# Motorcycle_ECU.net
KiCad netlist of a schematic drawn in Altium Designer
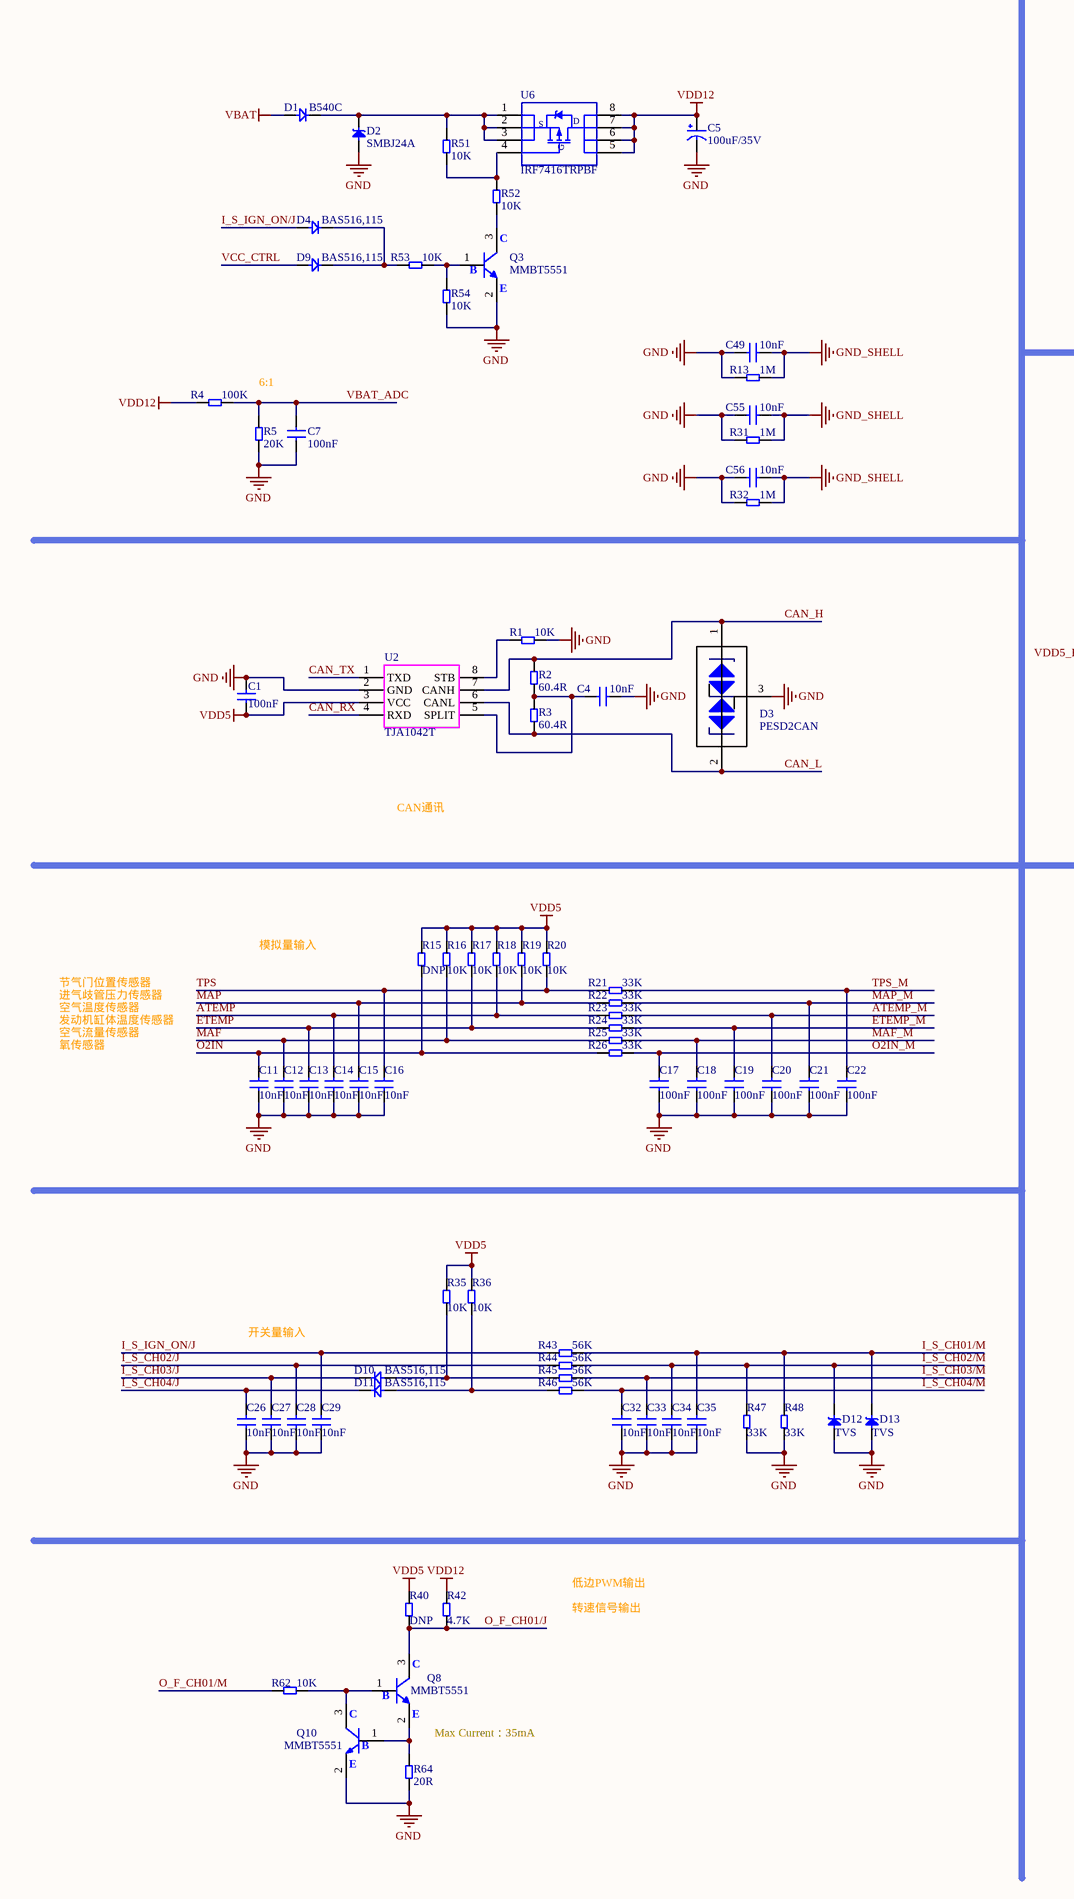
[diagram p0: Motorcycle_ECU.SchDoc, left]
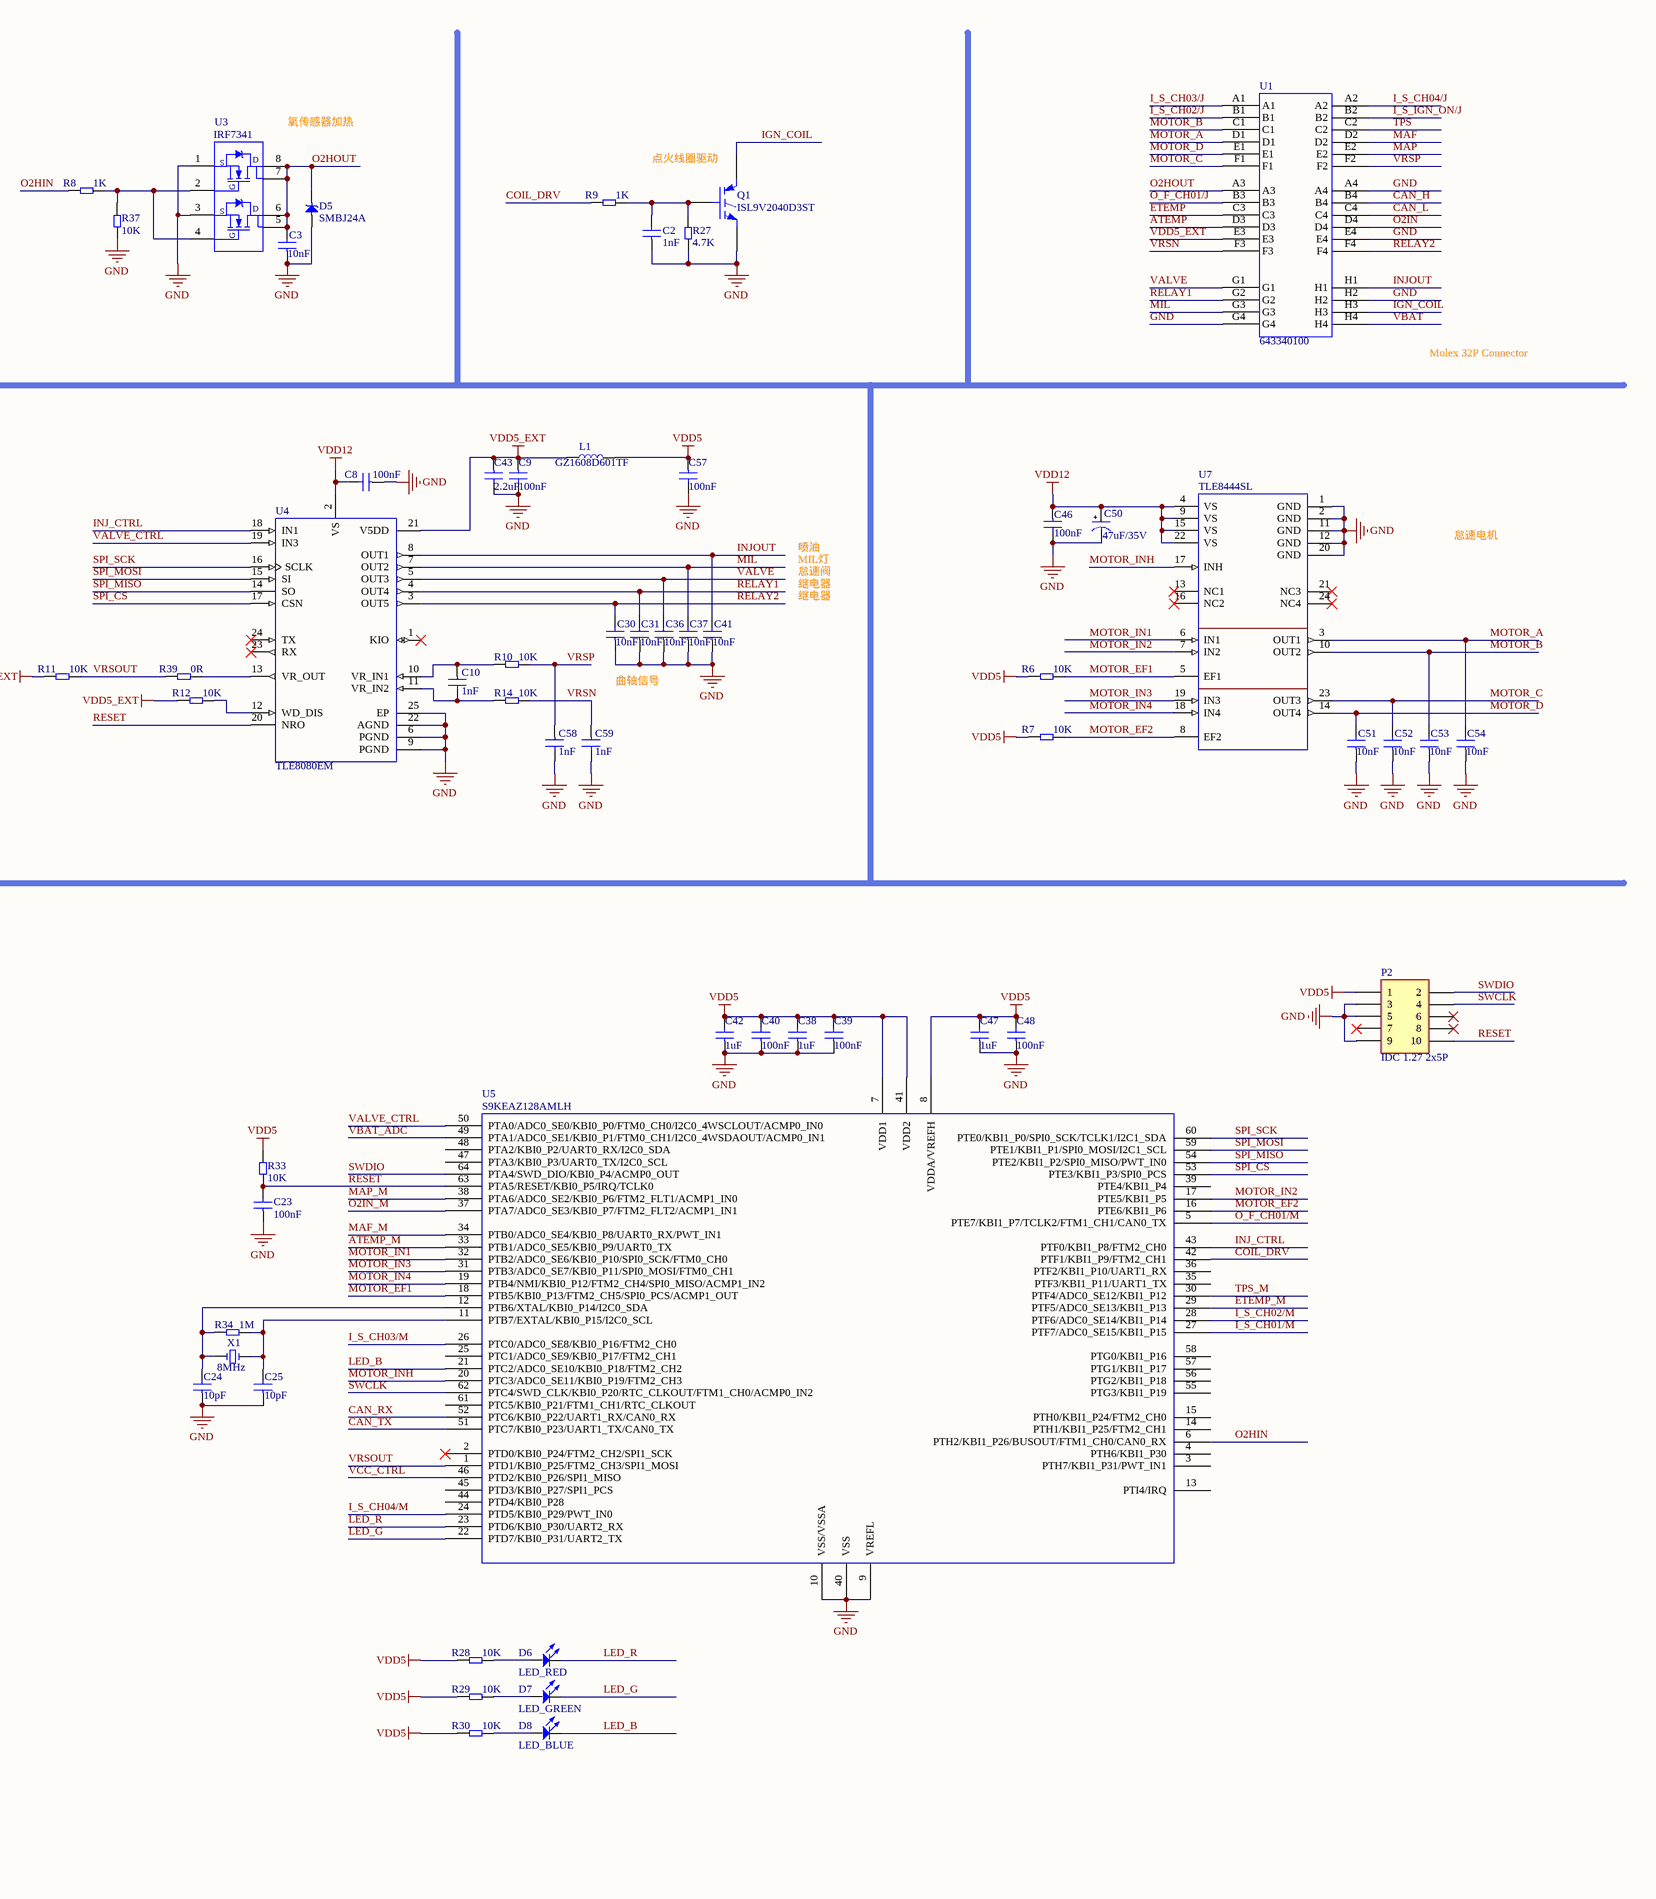
[diagram p1: Motorcycle_ECU.SchDoc, right]

(export (version "E")
  (design (tool "Eeschema 10.0.6"))
  (components
    (comp (ref "C1") (value "100nF") (footprint "C0603") (libsource (lib "mzy2364") (part "CAP")))
    (comp (ref "C2")
      (value "1nF")
      (footprint "C0603")
      (fields (field (name "VOLTAGE") "50V"))
      (libsource (lib "mzy2364") (part "CAP"))
    )
    (comp (ref "C3")
      (value "10nF")
      (footprint "C0603")
      (fields (field (name "VOLTAGE") "50V"))
      (libsource (lib "mzy2364") (part "CAP"))
    )
    (comp (ref "C4") (value "10nF") (footprint "C0603") (libsource (lib "mzy2364") (part "CAP")))
    (comp (ref "C5")
      (value "100uF/35V")
      (footprint "CM E(8*10.2)")
      (libsource (lib "mzy2364") (part "C POL"))
    )
    (comp (ref "C7")
      (value "100nF")
      (footprint "C0603")
      (fields (field (name "VOLTAGE") "50V"))
      (libsource (lib "mzy2364") (part "CAP"))
    )
    (comp (ref "C8")
      (value "100nF")
      (footprint "C0603")
      (fields (field (name "VOLTAGE") "50V"))
      (libsource (lib "mzy2364") (part "CAP"))
    )
    (comp (ref "C9")
      (value "100nF")
      (footprint "C0603")
      (fields (field (name "VOLTAGE") "50V"))
      (libsource (lib "mzy2364") (part "CAP"))
    )
    (comp (ref "C10")
      (value "1nF")
      (footprint "C0603")
      (fields (field (name "VOLTAGE") "50V"))
      (libsource (lib "mzy2364") (part "CAP"))
    )
    (comp (ref "C11")
      (value "10nF")
      (footprint "C0603")
      (fields (field (name "VOLTAGE") "50V"))
      (libsource (lib "mzy2364") (part "CAP"))
    )
    (comp (ref "C12")
      (value "10nF")
      (footprint "C0603")
      (fields (field (name "VOLTAGE") "50V"))
      (libsource (lib "mzy2364") (part "CAP"))
    )
    (comp (ref "C13")
      (value "10nF")
      (footprint "C0603")
      (fields (field (name "VOLTAGE") "50V"))
      (libsource (lib "mzy2364") (part "CAP"))
    )
    (comp (ref "C14")
      (value "10nF")
      (footprint "C0603")
      (fields (field (name "VOLTAGE") "50V"))
      (libsource (lib "mzy2364") (part "CAP"))
    )
    (comp (ref "C15")
      (value "10nF")
      (footprint "C0603")
      (fields (field (name "VOLTAGE") "50V"))
      (libsource (lib "mzy2364") (part "CAP"))
    )
    (comp (ref "C16")
      (value "10nF")
      (footprint "C0603")
      (fields (field (name "VOLTAGE") "50V"))
      (libsource (lib "mzy2364") (part "CAP"))
    )
    (comp (ref "C17")
      (value "100nF")
      (footprint "C0603")
      (fields (field (name "VOLTAGE") "50V"))
      (libsource (lib "mzy2364") (part "CAP"))
    )
    (comp (ref "C18")
      (value "100nF")
      (footprint "C0603")
      (fields (field (name "VOLTAGE") "50V"))
      (libsource (lib "mzy2364") (part "CAP"))
    )
    (comp (ref "C19")
      (value "100nF")
      (footprint "C0603")
      (fields (field (name "VOLTAGE") "50V"))
      (libsource (lib "mzy2364") (part "CAP"))
    )
    (comp (ref "C20")
      (value "100nF")
      (footprint "C0603")
      (fields (field (name "VOLTAGE") "50V"))
      (libsource (lib "mzy2364") (part "CAP"))
    )
    (comp (ref "C21")
      (value "100nF")
      (footprint "C0603")
      (fields (field (name "VOLTAGE") "50V"))
      (libsource (lib "mzy2364") (part "CAP"))
    )
    (comp (ref "C22")
      (value "100nF")
      (footprint "C0603")
      (fields (field (name "VOLTAGE") "50V"))
      (libsource (lib "mzy2364") (part "CAP"))
    )
    (comp (ref "C23")
      (value "100nF")
      (footprint "C0603")
      (fields (field (name "VOLTAGE") "50V"))
      (libsource (lib "mzy2364") (part "CAP"))
    )
    (comp (ref "C24") (value "10pF") (footprint "C0603") (libsource (lib "mzy2364") (part "CAP")))
    (comp (ref "C25") (value "10pF") (footprint "C0603") (libsource (lib "mzy2364") (part "CAP")))
    (comp (ref "C26")
      (value "10nF")
      (footprint "C0603")
      (fields (field (name "VOLTAGE") "50V"))
      (libsource (lib "mzy2364") (part "CAP"))
    )
    (comp (ref "C27")
      (value "10nF")
      (footprint "C0603")
      (fields (field (name "VOLTAGE") "50V"))
      (libsource (lib "mzy2364") (part "CAP"))
    )
    (comp (ref "C28")
      (value "10nF")
      (footprint "C0603")
      (fields (field (name "VOLTAGE") "50V"))
      (libsource (lib "mzy2364") (part "CAP"))
    )
    (comp (ref "C29")
      (value "10nF")
      (footprint "C0603")
      (fields (field (name "VOLTAGE") "50V"))
      (libsource (lib "mzy2364") (part "CAP"))
    )
    (comp (ref "C30")
      (value "10nF")
      (footprint "C0603")
      (fields (field (name "VOLTAGE") "50V"))
      (libsource (lib "mzy2364") (part "CAP"))
    )
    (comp (ref "C31")
      (value "10nF")
      (footprint "C0603")
      (fields (field (name "VOLTAGE") "50V"))
      (libsource (lib "mzy2364") (part "CAP"))
    )
    (comp (ref "C32")
      (value "10nF")
      (footprint "C0603")
      (fields (field (name "VOLTAGE") "50V"))
      (libsource (lib "mzy2364") (part "CAP"))
    )
    (comp (ref "C33")
      (value "10nF")
      (footprint "C0603")
      (fields (field (name "VOLTAGE") "50V"))
      (libsource (lib "mzy2364") (part "CAP"))
    )
    (comp (ref "C34")
      (value "10nF")
      (footprint "C0603")
      (fields (field (name "VOLTAGE") "50V"))
      (libsource (lib "mzy2364") (part "CAP"))
    )
    (comp (ref "C35")
      (value "10nF")
      (footprint "C0603")
      (fields (field (name "VOLTAGE") "50V"))
      (libsource (lib "mzy2364") (part "CAP"))
    )
    (comp (ref "C36")
      (value "10nF")
      (footprint "C0603")
      (fields (field (name "VOLTAGE") "50V"))
      (libsource (lib "mzy2364") (part "CAP"))
    )
    (comp (ref "C37")
      (value "10nF")
      (footprint "C0603")
      (fields (field (name "VOLTAGE") "50V"))
      (libsource (lib "mzy2364") (part "CAP"))
    )
    (comp (ref "C38")
      (value "1uF")
      (footprint "C0603")
      (fields (field (name "VOLTAGE") "50V"))
      (libsource (lib "mzy2364") (part "CAP"))
    )
    (comp (ref "C39")
      (value "100nF")
      (footprint "C0603")
      (fields (field (name "VOLTAGE") "50V"))
      (libsource (lib "mzy2364") (part "CAP"))
    )
    (comp (ref "C40")
      (value "100nF")
      (footprint "C0603")
      (fields (field (name "VOLTAGE") "50V"))
      (libsource (lib "mzy2364") (part "CAP"))
    )
    (comp (ref "C41")
      (value "10nF")
      (footprint "C0603")
      (fields (field (name "VOLTAGE") "50V"))
      (libsource (lib "mzy2364") (part "CAP"))
    )
    (comp (ref "C42")
      (value "1uF")
      (footprint "C0603")
      (fields (field (name "VOLTAGE") "50V"))
      (libsource (lib "mzy2364") (part "CAP"))
    )
    (comp (ref "C43")
      (value "2.2uF")
      (footprint "C0603")
      (fields (field (name "VOLTAGE") "50V"))
      (libsource (lib "mzy2364") (part "CAP"))
    )
    (comp (ref "C46")
      (value "100nF")
      (footprint "C0603")
      (fields (field (name "VOLTAGE") "50V"))
      (libsource (lib "mzy2364") (part "CAP"))
    )
    (comp (ref "C47")
      (value "1uF")
      (footprint "C0603")
      (fields (field (name "VOLTAGE") "50V"))
      (libsource (lib "mzy2364") (part "CAP"))
    )
    (comp (ref "C48")
      (value "100nF")
      (footprint "C0603")
      (fields (field (name "VOLTAGE") "50V"))
      (libsource (lib "mzy2364") (part "CAP"))
    )
    (comp (ref "C49")
      (value "10nF")
      (footprint "C0603")
      (fields (field (name "VOLTAGE") "50V"))
      (libsource (lib "mzy2364") (part "CAP"))
    )
    (comp (ref "C50")
      (value "47uF/35V")
      (footprint "CM D(6.3*7.7)")
      (libsource (lib "mzy2364") (part "C POL"))
    )
    (comp (ref "C51")
      (value "10nF")
      (footprint "C0603")
      (fields (field (name "VOLTAGE") "50V"))
      (libsource (lib "mzy2364") (part "CAP"))
    )
    (comp (ref "C52")
      (value "10nF")
      (footprint "C0603")
      (fields (field (name "VOLTAGE") "50V"))
      (libsource (lib "mzy2364") (part "CAP"))
    )
    (comp (ref "C53")
      (value "10nF")
      (footprint "C0603")
      (fields (field (name "VOLTAGE") "50V"))
      (libsource (lib "mzy2364") (part "CAP"))
    )
    (comp (ref "C54")
      (value "10nF")
      (footprint "C0603")
      (fields (field (name "VOLTAGE") "50V"))
      (libsource (lib "mzy2364") (part "CAP"))
    )
    (comp (ref "C55")
      (value "10nF")
      (footprint "C0603")
      (fields (field (name "VOLTAGE") "50V"))
      (libsource (lib "mzy2364") (part "CAP"))
    )
    (comp (ref "C56")
      (value "10nF")
      (footprint "C0603")
      (fields (field (name "VOLTAGE") "50V"))
      (libsource (lib "mzy2364") (part "CAP"))
    )
    (comp (ref "C57")
      (value "100nF")
      (footprint "C0603")
      (fields (field (name "VOLTAGE") "50V"))
      (libsource (lib "mzy2364") (part "CAP"))
    )
    (comp (ref "C58")
      (value "1nF")
      (footprint "C0603")
      (fields (field (name "VOLTAGE") "50V"))
      (libsource (lib "mzy2364") (part "CAP"))
    )
    (comp (ref "C59")
      (value "1nF")
      (footprint "C0603")
      (fields (field (name "VOLTAGE") "50V"))
      (libsource (lib "mzy2364") (part "CAP"))
    )
    (comp (ref "D1") (value "B540C") (footprint "SMC") (libsource (lib "mzy2364") (part "D")))
    (comp (ref "D2") (value "SMBJ24A") (footprint "SMB") (libsource (lib "mzy2364") (part "D TVS")))
    (comp (ref "D3") (value "PESD2CAN") (footprint "SOT23") (libsource (lib "EDC17_5644A") (part "PESD2CAN")))
    (comp (ref "D4") (value "BAS516,115") (footprint "SOD-523") (libsource (lib "mzy2364") (part "D")))
    (comp (ref "D5") (value "SMBJ24A") (footprint "SMB") (libsource (lib "mzy2364") (part "D TVS")))
    (comp (ref "D6") (value "LED_RED") (footprint "LED 0603") (libsource (lib "mzy2364") (part "LED")))
    (comp (ref "D7") (value "LED_GREEN") (footprint "LED 0603") (libsource (lib "mzy2364") (part "LED")))
    (comp (ref "D8") (value "LED_BLUE") (footprint "LED 0603") (libsource (lib "mzy2364") (part "LED")))
    (comp (ref "D9") (value "BAS516,115") (footprint "SOD-523") (libsource (lib "mzy2364") (part "D")))
    (comp (ref "D10") (value "BAS516,115") (footprint "SOD-523") (libsource (lib "mzy2364") (part "D")))
    (comp (ref "D11") (value "BAS516,115") (footprint "SOD-523") (libsource (lib "mzy2364") (part "D")))
    (comp (ref "D12") (value "TVS") (footprint "SOD-523") (libsource (lib "mzy2364") (part "D TVS")))
    (comp (ref "D13") (value "TVS") (footprint "SOD-523") (libsource (lib "mzy2364") (part "D TVS")))
    (comp (ref "L1") (value "GZ1608D601TF") (footprint "L_0603") (libsource (lib "mzy2364") (part "L")))
    (comp (ref "P2")
      (value "IDC 1.27 2x5P")
      (footprint "IDC-TH_10P-P1.27-X1270WV-2X05A-6TV01")
      (fields (field (name "PUBLISHER") "Altium Limited"))
      (libsource (lib "HRJDB_Lib") (part "Header 5X2"))
    )
    (comp (ref "Q1")
      (value "ISL9V2040D3ST")
      (footprint "TO252")
      (libsource (lib "mzy2364") (part "AOD5B65M1"))
    )
    (comp (ref "Q3") (value "MMBT5551") (footprint "SOT23") (libsource (lib "mzy2364") (part "NPN")))
    (comp (ref "Q8") (value "MMBT5551") (footprint "SOT23") (libsource (lib "mzy2364") (part "NPN")))
    (comp (ref "Q10") (value "MMBT5551") (footprint "SOT23") (libsource (lib "mzy2364") (part "NPN_1")))
    (comp (ref "R1") (value "10K") (footprint "RES0603") (libsource (lib "mzy2364") (part "RES")))
    (comp (ref "R2") (value "60.4R") (footprint "RES0603") (libsource (lib "mzy2364") (part "RES")))
    (comp (ref "R3") (value "60.4R") (footprint "RES0603") (libsource (lib "mzy2364") (part "RES")))
    (comp (ref "R4") (value "100K") (footprint "RES0603") (libsource (lib "mzy2364") (part "RES")))
    (comp (ref "R5") (value "20K") (footprint "RES0603") (libsource (lib "mzy2364") (part "RES")))
    (comp (ref "R6") (value "10K") (footprint "RES0603") (libsource (lib "mzy2364") (part "RES")))
    (comp (ref "R7") (value "10K") (footprint "RES0603") (libsource (lib "mzy2364") (part "RES")))
    (comp (ref "R8") (value "1K") (footprint "RES0603") (libsource (lib "mzy2364") (part "RES")))
    (comp (ref "R9") (value "1K") (footprint "RES0603") (libsource (lib "mzy2364") (part "RES")))
    (comp (ref "R10") (value "10K") (footprint "RES0603") (libsource (lib "mzy2364") (part "RES")))
    (comp (ref "R11") (value "10K") (footprint "RES0603") (libsource (lib "mzy2364") (part "RES")))
    (comp (ref "R12") (value "10K") (footprint "RES0603") (libsource (lib "mzy2364") (part "RES")))
    (comp (ref "R13") (value "1M") (footprint "RES0603") (libsource (lib "mzy2364") (part "RES")))
    (comp (ref "R14") (value "10K") (footprint "RES0603") (libsource (lib "mzy2364") (part "RES")))
    (comp (ref "R15") (value "DNP") (footprint "RES0603") (libsource (lib "mzy2364") (part "RES")))
    (comp (ref "R16") (value "10K") (footprint "RES0603") (libsource (lib "mzy2364") (part "RES")))
    (comp (ref "R17") (value "10K") (footprint "RES0603") (libsource (lib "mzy2364") (part "RES")))
    (comp (ref "R18") (value "10K") (footprint "RES0603") (libsource (lib "mzy2364") (part "RES")))
    (comp (ref "R19") (value "10K") (footprint "RES0603") (libsource (lib "mzy2364") (part "RES")))
    (comp (ref "R20") (value "10K") (footprint "RES0603") (libsource (lib "mzy2364") (part "RES")))
    (comp (ref "R21") (value "33K") (footprint "RES0603") (libsource (lib "mzy2364") (part "RES")))
    (comp (ref "R22") (value "33K") (footprint "RES0603") (libsource (lib "mzy2364") (part "RES")))
    (comp (ref "R23") (value "33K") (footprint "RES0603") (libsource (lib "mzy2364") (part "RES")))
    (comp (ref "R24") (value "33K") (footprint "RES0603") (libsource (lib "mzy2364") (part "RES")))
    (comp (ref "R25") (value "33K") (footprint "RES0603") (libsource (lib "mzy2364") (part "RES")))
    (comp (ref "R26") (value "33K") (footprint "RES0603") (libsource (lib "mzy2364") (part "RES")))
    (comp (ref "R27") (value "4.7K") (footprint "RES0603") (libsource (lib "mzy2364") (part "RES")))
    (comp (ref "R28") (value "10K") (footprint "RES0603") (libsource (lib "mzy2364") (part "RES")))
    (comp (ref "R29") (value "10K") (footprint "RES0603") (libsource (lib "mzy2364") (part "RES")))
    (comp (ref "R30") (value "10K") (footprint "RES0603") (libsource (lib "mzy2364") (part "RES")))
    (comp (ref "R31") (value "1M") (footprint "RES0603") (libsource (lib "mzy2364") (part "RES")))
    (comp (ref "R32") (value "1M") (footprint "RES0603") (libsource (lib "mzy2364") (part "RES")))
    (comp (ref "R33") (value "10K") (footprint "RES0603") (libsource (lib "mzy2364") (part "RES")))
    (comp (ref "R34") (value "1M") (footprint "RES0603") (libsource (lib "mzy2364") (part "RES")))
    (comp (ref "R35") (value "10K") (footprint "RES0603") (libsource (lib "mzy2364") (part "RES")))
    (comp (ref "R36") (value "10K") (footprint "RES0603") (libsource (lib "mzy2364") (part "RES")))
    (comp (ref "R37") (value "10K") (footprint "RES0603") (libsource (lib "mzy2364") (part "RES")))
    (comp (ref "R39") (value "0R") (footprint "RES0603") (libsource (lib "mzy2364") (part "RES")))
    (comp (ref "R40") (value "DNP") (footprint "RES0603") (libsource (lib "mzy2364") (part "RES")))
    (comp (ref "R42") (value "4.7K") (footprint "RES0603") (libsource (lib "mzy2364") (part "RES")))
    (comp (ref "R43") (value "56K") (footprint "RES0603") (libsource (lib "mzy2364") (part "RES")))
    (comp (ref "R44") (value "56K") (footprint "RES0603") (libsource (lib "mzy2364") (part "RES")))
    (comp (ref "R45") (value "56K") (footprint "RES0603") (libsource (lib "mzy2364") (part "RES")))
    (comp (ref "R46") (value "56K") (footprint "RES0603") (libsource (lib "mzy2364") (part "RES")))
    (comp (ref "R47") (value "33K") (footprint "RES0603") (libsource (lib "mzy2364") (part "RES")))
    (comp (ref "R48") (value "33K") (footprint "RES0603") (libsource (lib "mzy2364") (part "RES")))
    (comp (ref "R51") (value "10K") (footprint "RES0603") (libsource (lib "mzy2364") (part "RES")))
    (comp (ref "R52") (value "10K") (footprint "RES0603") (libsource (lib "mzy2364") (part "RES")))
    (comp (ref "R53") (value "10K") (footprint "RES0603") (libsource (lib "mzy2364") (part "RES")))
    (comp (ref "R54") (value "10K") (footprint "RES0603") (libsource (lib "mzy2364") (part "RES")))
    (comp (ref "R62") (value "10K") (footprint "RES0603") (libsource (lib "mzy2364") (part "RES")))
    (comp (ref "R64") (value "20R") (footprint "RES0603") (libsource (lib "mzy2364") (part "RES")))
    (comp (ref "U1")
      (value "643340100")
      (footprint "MOLEX-32P_SHARP_1")
      (description "MOLEX 32P接插件")
      (libsource (lib "mzy2364") (part "643340100"))
    )
    (comp (ref "U2")
      (value "TJA1042T")
      (footprint "SOIC8-150MIL")
      (description "CAN收发器")
      (libsource (lib "mzy2364") (part "TJA1042T"))
    )
    (comp (ref "U3")
      (value "IRF7341")
      (footprint "SOIC8-150MIL")
      (description "NMOS 双通道")
      (libsource (lib "mzy2364") (part "AO4800"))
    )
    (comp (ref "U4")
      (value "TLE8080EM")
      (footprint "INF-PG-SSOP-24-4")
      (description "Engine Management IC for Small Engine, 6 to 18 V Supply, PG-SSOP-24-4, Reel, Green")
      (fields (field (name "MANUFACTURER") "Infineon"))
      (libsource (lib "mzy2364") (part "TLE8080EM"))
    )
    (comp (ref "U5")
      (value "S9KEAZ128AMLH")
      (footprint "LQFP64-0.5")
      (libsource (lib "mzy2364") (part "S9KEAZ64AMLH"))
    )
    (comp (ref "U6")
      (value "IRF7416TRPBF")
      (footprint "SOIC8-150MIL")
      (libsource (lib "mzy2364") (part "FDS4435BZ"))
    )
    (comp (ref "U7")
      (value "TLE8444SL")
      (footprint "INF-PG-SSOP-24")
      (description "Quad Half-Bridge Driver IC")
      (fields (field (name "MANUFACTURER") "Infineon Technologies"))
      (libsource (lib "mzy2364") (part "TLE8444SL"))
    )
    (comp (ref "X1") (value "8MHz") (footprint "OSC 5032-2P") (libsource (lib "mzy2364") (part "XTAL-2P")))
  )
  (nets
    (net (code "1") (name "/ATEMP") (class "Default")
      (node (ref "C14") (pin "2") (pinfunction "2_2") (pintype "passive"))
      (node (ref "R18") (pin "1") (pinfunction "BST_1") (pintype "passive"))
      (node (ref "R23") (pin "1") (pinfunction "BST_1") (pintype "passive"))
      (node (ref "U1") (pin "D3") (pinfunction "D3_D3") (pintype "passive"))
    )
    (net (code "2") (name "/ATEMP_M") (class "Default")
      (node (ref "C20") (pin "2") (pinfunction "2_2") (pintype "passive"))
      (node (ref "R23") (pin "2") (pinfunction "BST_2") (pintype "passive"))
      (node (ref "U5") (pin "33") (pinfunction "PTB1/ADC0_SE5/KBI0_P9/UART0_TX_33") (pintype "passive"))
    )
    (net (code "3") (name "/CAN_H") (class "Default")
      (node (ref "D3") (pin "1") (pintype "passive"))
      (node (ref "R2") (pin "2") (pinfunction "BST_2") (pintype "passive"))
      (node (ref "U1") (pin "B4") (pinfunction "B4_B4") (pintype "passive"))
      (node (ref "U2") (pin "7") (pinfunction "CANH_7") (pintype "passive"))
    )
    (net (code "4") (name "/CAN_L") (class "Default")
      (node (ref "D3") (pin "2") (pintype "passive"))
      (node (ref "R3") (pin "1") (pinfunction "BST_1") (pintype "passive"))
      (node (ref "U1") (pin "C4") (pinfunction "C4_C4") (pintype "passive"))
      (node (ref "U2") (pin "6") (pinfunction "CANL_6") (pintype "passive"))
    )
    (net (code "5") (name "/CAN_RX") (class "Default")
      (node (ref "U2") (pin "4") (pinfunction "RXD_4") (pintype "passive"))
      (node (ref "U5") (pin "52") (pinfunction "PTC6/KBI0_P22/UART1_RX/CAN0_RX_52") (pintype "passive"))
    )
    (net (code "6") (name "/CAN_TX") (class "Default")
      (node (ref "U2") (pin "1") (pinfunction "TXD_1") (pintype "passive"))
      (node (ref "U5") (pin "51") (pinfunction "PTC7/KBI0_P23/UART1_TX/CAN0_TX_51") (pintype "passive"))
    )
    (net (code "7") (name "/COIL_DRV") (class "Default")
      (node (ref "R9") (pin "1") (pinfunction "BST_1") (pintype "passive"))
      (node (ref "U5") (pin "42") (pinfunction "PTF1/KBI1_P9/FTM2_CH1_42") (pintype "passive"))
    )
    (net (code "8") (name "/ETEMP") (class "Default")
      (node (ref "C13") (pin "2") (pinfunction "2_2") (pintype "passive"))
      (node (ref "R17") (pin "1") (pinfunction "BST_1") (pintype "passive"))
      (node (ref "R24") (pin "1") (pinfunction "BST_1") (pintype "passive"))
      (node (ref "U1") (pin "C3") (pinfunction "C3_C3") (pintype "passive"))
    )
    (net (code "9") (name "/ETEMP_M") (class "Default")
      (node (ref "C19") (pin "2") (pinfunction "2_2") (pintype "passive"))
      (node (ref "R24") (pin "2") (pinfunction "BST_2") (pintype "passive"))
      (node (ref "U5") (pin "29") (pinfunction "PTF5/ADC0_SE13/KBI1_P13_29") (pintype "passive"))
    )
    (net (code "10") (name "/IGN_COIL") (class "Default")
      (node (ref "Q1") (pin "2") (pinfunction "C_2") (pintype "passive"))
      (node (ref "U1") (pin "H3") (pinfunction "H3_H3") (pintype "passive"))
    )
    (net (code "11") (name "/INJOUT") (class "Default")
      (node (ref "C41") (pin "2") (pinfunction "2_2") (pintype "passive"))
      (node (ref "U1") (pin "H1") (pinfunction "H1_H1") (pintype "passive"))
      (node (ref "U4") (pin "8") (pinfunction "OUT1_8") (pintype "output"))
    )
    (net (code "12") (name "/INJ_CTRL") (class "Default")
      (node (ref "U4") (pin "18") (pinfunction "IN1_18") (pintype "input"))
      (node (ref "U5") (pin "43") (pinfunction "PTF0/KBI1_P8/FTM2_CH0_43") (pintype "passive"))
    )
    (net (code "13") (name "/I_S_CH01{slash}M") (class "Default")
      (node (ref "C35") (pin "2") (pinfunction "2_2") (pintype "passive"))
      (node (ref "D13") (pin "2") (pintype "passive"))
      (node (ref "R43") (pin "2") (pinfunction "BST_2") (pintype "passive"))
      (node (ref "R48") (pin "2") (pinfunction "BST_2") (pintype "passive"))
      (node (ref "U5") (pin "27") (pinfunction "PTF7/ADC0_SE15/KBI1_P15_27") (pintype "passive"))
    )
    (net (code "14") (name "/I_S_CH02{slash}J") (class "Default")
      (node (ref "C28") (pin "2") (pinfunction "2_2") (pintype "passive"))
      (node (ref "R44") (pin "1") (pinfunction "BST_1") (pintype "passive"))
      (node (ref "U1") (pin "B1") (pinfunction "B1_B1") (pintype "passive"))
    )
    (net (code "15") (name "/I_S_CH02{slash}M") (class "Default")
      (node (ref "C34") (pin "2") (pinfunction "2_2") (pintype "passive"))
      (node (ref "D12") (pin "2") (pintype "passive"))
      (node (ref "R44") (pin "2") (pinfunction "BST_2") (pintype "passive"))
      (node (ref "R47") (pin "2") (pinfunction "BST_2") (pintype "passive"))
      (node (ref "U5") (pin "28") (pinfunction "PTF6/ADC0_SE14/KBI1_P14_28") (pintype "passive"))
    )
    (net (code "16") (name "/I_S_CH03{slash}J") (class "Default")
      (node (ref "C27") (pin "2") (pinfunction "2_2") (pintype "passive"))
      (node (ref "D10") (pin "2") (pintype "passive"))
      (node (ref "U1") (pin "A1") (pinfunction "A1_A1") (pintype "passive"))
    )
    (net (code "17") (name "/I_S_CH03{slash}M") (class "Default")
      (node (ref "C33") (pin "2") (pinfunction "2_2") (pintype "passive"))
      (node (ref "R45") (pin "2") (pinfunction "BST_2") (pintype "passive"))
      (node (ref "U5") (pin "26") (pinfunction "PTC0/ADC0_SE8/KBI0_P16/FTM2_CH0_26") (pintype "passive"))
    )
    (net (code "18") (name "/I_S_CH04{slash}J") (class "Default")
      (node (ref "C26") (pin "2") (pinfunction "2_2") (pintype "passive"))
      (node (ref "D11") (pin "2") (pintype "passive"))
      (node (ref "U1") (pin "A2") (pinfunction "A2_A2") (pintype "passive"))
    )
    (net (code "19") (name "/I_S_CH04{slash}M") (class "Default")
      (node (ref "C32") (pin "2") (pinfunction "2_2") (pintype "passive"))
      (node (ref "R46") (pin "2") (pinfunction "BST_2") (pintype "passive"))
      (node (ref "U5") (pin "24") (pinfunction "PTD5/KBI0_P29/PWT_IN0_24") (pintype "passive"))
    )
    (net (code "20") (name "/I_S_IGN_ON{slash}J") (class "Default")
      (node (ref "C29") (pin "2") (pinfunction "2_2") (pintype "passive"))
      (node (ref "D4") (pin "1") (pintype "passive"))
      (node (ref "R43") (pin "1") (pinfunction "BST_1") (pintype "passive"))
      (node (ref "U1") (pin "B2") (pinfunction "B2_B2") (pintype "passive"))
    )
    (net (code "21") (name "/LED_B") (class "Default")
      (node (ref "D8") (pin "2") (pinfunction "K_2") (pintype "passive"))
      (node (ref "U5") (pin "21") (pinfunction "PTC2/ADC0_SE10/KBI0_P18/FTM2_CH2_21") (pintype "passive"))
    )
    (net (code "22") (name "/LED_G") (class "Default")
      (node (ref "D7") (pin "2") (pinfunction "K_2") (pintype "passive"))
      (node (ref "U5") (pin "22") (pinfunction "PTD7/KBI0_P31/UART2_TX_22") (pintype "passive"))
    )
    (net (code "23") (name "/LED_R") (class "Default")
      (node (ref "D6") (pin "2") (pinfunction "K_2") (pintype "passive"))
      (node (ref "U5") (pin "23") (pinfunction "PTD6/KBI0_P30/UART2_RX_23") (pintype "passive"))
    )
    (net (code "24") (name "/MAF") (class "Default")
      (node (ref "C12") (pin "2") (pinfunction "2_2") (pintype "passive"))
      (node (ref "R16") (pin "1") (pinfunction "BST_1") (pintype "passive"))
      (node (ref "R25") (pin "1") (pinfunction "BST_1") (pintype "passive"))
      (node (ref "U1") (pin "D2") (pinfunction "D2_D2") (pintype "passive"))
    )
    (net (code "25") (name "/MAF_M") (class "Default")
      (node (ref "C18") (pin "2") (pinfunction "2_2") (pintype "passive"))
      (node (ref "R25") (pin "2") (pinfunction "BST_2") (pintype "passive"))
      (node (ref "U5") (pin "34") (pinfunction "PTB0/ADC0_SE4/KBI0_P8/UART0_RX/PWT_IN1_34") (pintype "passive"))
    )
    (net (code "26") (name "/MAP") (class "Default")
      (node (ref "C15") (pin "2") (pinfunction "2_2") (pintype "passive"))
      (node (ref "R19") (pin "1") (pinfunction "BST_1") (pintype "passive"))
      (node (ref "R22") (pin "1") (pinfunction "BST_1") (pintype "passive"))
      (node (ref "U1") (pin "E2") (pinfunction "E2_E2") (pintype "passive"))
    )
    (net (code "27") (name "/MAP_M") (class "Default")
      (node (ref "C21") (pin "2") (pinfunction "2_2") (pintype "passive"))
      (node (ref "R22") (pin "2") (pinfunction "BST_2") (pintype "passive"))
      (node (ref "U5") (pin "38") (pinfunction "PTA6/ADC0_SE2/KBI0_P6/FTM2_FLT1/ACMP1_IN0_38") (pintype "passive"))
    )
    (net (code "28") (name "/MIL") (class "Default")
      (node (ref "C37") (pin "2") (pinfunction "2_2") (pintype "passive"))
      (node (ref "U1") (pin "G3") (pinfunction "G3_G3") (pintype "passive"))
      (node (ref "U4") (pin "7") (pinfunction "OUT2_7") (pintype "output"))
    )
    (net (code "29") (name "/MOTOR_A") (class "Default")
      (node (ref "C54") (pin "2") (pinfunction "2_2") (pintype "passive"))
      (node (ref "U1") (pin "D1") (pinfunction "D1_D1") (pintype "passive"))
      (node (ref "U7") (pin "3") (pinfunction "OUT1_3") (pintype "output"))
    )
    (net (code "30") (name "/MOTOR_B") (class "Default")
      (node (ref "C53") (pin "2") (pinfunction "2_2") (pintype "passive"))
      (node (ref "U1") (pin "C1") (pinfunction "C1_C1") (pintype "passive"))
      (node (ref "U7") (pin "10") (pinfunction "OUT2_10") (pintype "output"))
    )
    (net (code "31") (name "/MOTOR_C") (class "Default")
      (node (ref "C52") (pin "2") (pinfunction "2_2") (pintype "passive"))
      (node (ref "U1") (pin "F1") (pinfunction "F1_F1") (pintype "passive"))
      (node (ref "U7") (pin "23") (pinfunction "OUT3_23") (pintype "output"))
    )
    (net (code "32") (name "/MOTOR_D") (class "Default")
      (node (ref "C51") (pin "2") (pinfunction "2_2") (pintype "passive"))
      (node (ref "U1") (pin "E1") (pinfunction "E1_E1") (pintype "passive"))
      (node (ref "U7") (pin "14") (pinfunction "OUT4_14") (pintype "output"))
    )
    (net (code "33") (name "/MOTOR_EF1") (class "Default")
      (node (ref "R6") (pin "1") (pinfunction "BST_1") (pintype "passive"))
      (node (ref "U5") (pin "18") (pinfunction "PTB5/KBI0_P13/FTM2_CH5/SPI0_PCS/ACMP1_OUT_18") (pintype "passive"))
      (node (ref "U7") (pin "5") (pinfunction "EF1_5") (pintype "open_collector"))
    )
    (net (code "34") (name "/MOTOR_EF2") (class "Default")
      (node (ref "R7") (pin "1") (pinfunction "BST_1") (pintype "passive"))
      (node (ref "U5") (pin "16") (pinfunction "PTE6/KBI1_P6_16") (pintype "passive"))
      (node (ref "U7") (pin "8") (pinfunction "EF2_8") (pintype "open_collector"))
    )
    (net (code "35") (name "/MOTOR_IN1") (class "Default")
      (node (ref "U5") (pin "32") (pinfunction "PTB2/ADC0_SE6/KBI0_P10/SPI0_SCK/FTM0_CH0_32") (pintype "passive"))
      (node (ref "U7") (pin "6") (pinfunction "IN1_6") (pintype "input"))
    )
    (net (code "36") (name "/MOTOR_IN2") (class "Default")
      (node (ref "U5") (pin "17") (pinfunction "PTE5/KBI1_P5_17") (pintype "passive"))
      (node (ref "U7") (pin "7") (pinfunction "IN2_7") (pintype "input"))
    )
    (net (code "37") (name "/MOTOR_IN3") (class "Default")
      (node (ref "U5") (pin "31") (pinfunction "PTB3/ADC0_SE7/KBI0_P11/SPI0_MOSI/FTM0_CH1_31") (pintype "passive"))
      (node (ref "U7") (pin "19") (pinfunction "IN3_19") (pintype "input"))
    )
    (net (code "38") (name "/MOTOR_IN4") (class "Default")
      (node (ref "U5") (pin "19") (pinfunction "PTB4/NMI/KBI0_P12/FTM2_CH4/SPI0_MISO/ACMP1_IN2_19") (pintype "passive"))
      (node (ref "U7") (pin "18") (pinfunction "IN4_18") (pintype "input"))
    )
    (net (code "39") (name "/MOTOR_INH") (class "Default")
      (node (ref "U5") (pin "20") (pinfunction "PTC3/ADC0_SE11/KBI0_P19/FTM2_CH3_20") (pintype "passive"))
      (node (ref "U7") (pin "17") (pinfunction "INH_17") (pintype "input"))
    )
    (net (code "40") (name "/O2HIN") (class "Default")
      (node (ref "R8") (pin "1") (pinfunction "BST_1") (pintype "passive"))
      (node (ref "U5") (pin "6") (pinfunction "PTH2/KBI1_P26/BUSOUT/FTM1_CH0/CAN0_RX_6") (pintype "passive"))
    )
    (net (code "41") (name "/O2HOUT") (class "Default")
      (node (ref "C3") (pin "2") (pinfunction "2_2") (pintype "passive"))
      (node (ref "D5") (pin "2") (pintype "passive"))
      (node (ref "U1") (pin "A3") (pinfunction "A3_A3") (pintype "passive"))
      (node (ref "U3") (pin "5") (pinfunction "D1_5") (pintype "passive"))
      (node (ref "U3") (pin "6") (pinfunction "D1_6") (pintype "passive"))
      (node (ref "U3") (pin "7") (pinfunction "D2_7") (pintype "passive"))
      (node (ref "U3") (pin "8") (pinfunction "D2_8") (pintype "passive"))
    )
    (net (code "42") (name "/O2IN") (class "Default")
      (node (ref "C11") (pin "2") (pinfunction "2_2") (pintype "passive"))
      (node (ref "R15") (pin "1") (pinfunction "BST_1") (pintype "passive"))
      (node (ref "R26") (pin "1") (pinfunction "BST_1") (pintype "passive"))
      (node (ref "U1") (pin "D4") (pinfunction "D4_D4") (pintype "passive"))
    )
    (net (code "43") (name "/O2IN_M") (class "Default")
      (node (ref "C17") (pin "2") (pinfunction "2_2") (pintype "passive"))
      (node (ref "R26") (pin "2") (pinfunction "BST_2") (pintype "passive"))
      (node (ref "U5") (pin "37") (pinfunction "PTA7/ADC0_SE3/KBI0_P7/FTM2_FLT2/ACMP1_IN1_37") (pintype "passive"))
    )
    (net (code "44") (name "/O_F_CH01{slash}J") (class "Default")
      (node (ref "Q8") (pin "3") (pinfunction "C_3") (pintype "passive"))
      (node (ref "R40") (pin "1") (pinfunction "BST_1") (pintype "passive"))
      (node (ref "R42") (pin "1") (pinfunction "BST_1") (pintype "passive"))
      (node (ref "U1") (pin "B3") (pinfunction "B3_B3") (pintype "passive"))
    )
    (net (code "45") (name "/O_F_CH01{slash}M") (class "Default")
      (node (ref "R62") (pin "2") (pinfunction "BST_2") (pintype "passive"))
      (node (ref "U5") (pin "5") (pinfunction "PTE7/KBI1_P7/TCLK2/FTM1_CH1/CAN0_TX_5") (pintype "passive"))
    )
    (net (code "46") (name "/RELAY1") (class "Default")
      (node (ref "C31") (pin "2") (pinfunction "2_2") (pintype "passive"))
      (node (ref "U1") (pin "G2") (pinfunction "G2_G2") (pintype "passive"))
      (node (ref "U4") (pin "4") (pinfunction "OUT4_4") (pintype "output"))
    )
    (net (code "47") (name "/RELAY2") (class "Default")
      (node (ref "C30") (pin "2") (pinfunction "2_2") (pintype "passive"))
      (node (ref "U1") (pin "F4") (pinfunction "F4_F4") (pintype "passive"))
      (node (ref "U4") (pin "3") (pinfunction "OUT5_3") (pintype "output"))
    )
    (net (code "48") (name "/RESET") (class "Default")
      (node (ref "C23") (pin "2") (pinfunction "2_2") (pintype "passive"))
      (node (ref "P2") (pin "10") (pinfunction "10_10") (pintype "passive"))
      (node (ref "R33") (pin "1") (pinfunction "BST_1") (pintype "passive"))
      (node (ref "U4") (pin "20") (pinfunction "NRO_20") (pintype "open_collector"))
      (node (ref "U5") (pin "63") (pinfunction "PTA5/RESET/KBI0_P5/IRQ/TCLK0_63") (pintype "passive"))
    )
    (net (code "49") (name "/SPI_CS") (class "Default")
      (node (ref "U4") (pin "17") (pinfunction "CSN_17") (pintype "input"))
      (node (ref "U5") (pin "53") (pinfunction "PTE3/KBI1_P3/SPI0_PCS_53") (pintype "passive"))
    )
    (net (code "50") (name "/SPI_MISO") (class "Default")
      (node (ref "U4") (pin "14") (pinfunction "SO_14") (pintype "tri_state"))
      (node (ref "U5") (pin "54") (pinfunction "PTE2/KBI1_P2/SPI0_MISO/PWT_IN0_54") (pintype "passive"))
    )
    (net (code "51") (name "/SPI_MOSI") (class "Default")
      (node (ref "U4") (pin "15") (pinfunction "SI_15") (pintype "input"))
      (node (ref "U5") (pin "59") (pinfunction "PTE1/KBI1_P1/SPI0_MOSI/I2C1_SCL_59") (pintype "passive"))
    )
    (net (code "52") (name "/SPI_SCK") (class "Default")
      (node (ref "U4") (pin "16") (pinfunction "SCLK_16") (pintype "input"))
      (node (ref "U5") (pin "60") (pinfunction "PTE0/KBI1_P0/SPI0_SCK/TCLK1/I2C1_SDA_60") (pintype "passive"))
    )
    (net (code "53") (name "/SWCLK") (class "Default")
      (node (ref "P2") (pin "4") (pinfunction "4_4") (pintype "passive"))
      (node (ref "U5") (pin "62") (pinfunction "PTC4/SWD_CLK/KBI0_P20/RTC_CLKOUT/FTM1_CH0/ACMP0_IN2_62") (pintype "passive"))
    )
    (net (code "54") (name "/SWDIO") (class "Default")
      (node (ref "P2") (pin "2") (pinfunction "2_2") (pintype "passive"))
      (node (ref "U5") (pin "64") (pinfunction "PTA4/SWD_DIO/KBI0_P4/ACMP0_OUT_64") (pintype "passive"))
    )
    (net (code "55") (name "/TPS") (class "Default")
      (node (ref "C16") (pin "2") (pinfunction "2_2") (pintype "passive"))
      (node (ref "R20") (pin "1") (pinfunction "BST_1") (pintype "passive"))
      (node (ref "R21") (pin "1") (pinfunction "BST_1") (pintype "passive"))
      (node (ref "U1") (pin "C2") (pinfunction "C2_C2") (pintype "passive"))
    )
    (net (code "56") (name "/TPS_M") (class "Default")
      (node (ref "C22") (pin "2") (pinfunction "2_2") (pintype "passive"))
      (node (ref "R21") (pin "2") (pinfunction "BST_2") (pintype "passive"))
      (node (ref "U5") (pin "30") (pinfunction "PTF4/ADC0_SE12/KBI1_P12_30") (pintype "passive"))
    )
    (net (code "57") (name "/VALVE") (class "Default")
      (node (ref "C36") (pin "2") (pinfunction "2_2") (pintype "passive"))
      (node (ref "U1") (pin "G1") (pinfunction "G1_G1") (pintype "passive"))
      (node (ref "U4") (pin "5") (pinfunction "OUT3_5") (pintype "output"))
    )
    (net (code "58") (name "/VALVE_CTRL") (class "Default")
      (node (ref "U4") (pin "19") (pinfunction "IN3_19") (pintype "input"))
      (node (ref "U5") (pin "50") (pinfunction "PTA0/ADC0_SE0/KBI0_P0/FTM0_CH0/I2C0_4WSCLOUT/ACMP0_IN0_50") (pintype "passive"))
    )
    (net (code "59") (name "/VBAT_ADC") (class "Default")
      (node (ref "C7") (pin "2") (pinfunction "2_2") (pintype "passive"))
      (node (ref "R4") (pin "2") (pinfunction "BST_2") (pintype "passive"))
      (node (ref "R5") (pin "2") (pinfunction "BST_2") (pintype "passive"))
      (node (ref "U5") (pin "49") (pinfunction "PTA1/ADC0_SE1/KBI0_P1/FTM0_CH1/I2C0_4WSDAOUT/ACMP0_IN1_49") (pintype "passive"))
    )
    (net (code "60") (name "/VCC_CTRL") (class "Default")
      (node (ref "D9") (pin "1") (pintype "passive"))
      (node (ref "U5") (pin "46") (pinfunction "PTD2/KBI0_P26/SPI1_MISO_46") (pintype "passive"))
    )
    (net (code "61") (name "/VRSN") (class "Default")
      (node (ref "C59") (pin "1") (pinfunction "1_1") (pintype "passive"))
      (node (ref "R14") (pin "1") (pinfunction "BST_1") (pintype "passive"))
      (node (ref "U1") (pin "F3") (pinfunction "F3_F3") (pintype "passive"))
    )
    (net (code "62") (name "/VRSOUT") (class "Default")
      (node (ref "R11") (pin "1") (pinfunction "BST_1") (pintype "passive"))
      (node (ref "R39") (pin "2") (pinfunction "BST_2") (pintype "passive"))
      (node (ref "U5") (pin "1") (pinfunction "PTD1/KBI0_P25/FTM2_CH3/SPI1_MOSI_1") (pintype "passive"))
    )
    (net (code "63") (name "/VRSP") (class "Default")
      (node (ref "C58") (pin "1") (pinfunction "1_1") (pintype "passive"))
      (node (ref "R10") (pin "1") (pinfunction "BST_1") (pintype "passive"))
      (node (ref "U1") (pin "F2") (pinfunction "F2_F2") (pintype "passive"))
    )
    (net (code "64") (name "GND") (class "Default")
      (node (ref "C1") (pin "2") (pinfunction "2_2") (pintype "passive"))
      (node (ref "C11") (pin "1") (pinfunction "1_1") (pintype "passive"))
      (node (ref "C12") (pin "1") (pinfunction "1_1") (pintype "passive"))
      (node (ref "C13") (pin "1") (pinfunction "1_1") (pintype "passive"))
      (node (ref "C14") (pin "1") (pinfunction "1_1") (pintype "passive"))
      (node (ref "C15") (pin "1") (pinfunction "1_1") (pintype "passive"))
      (node (ref "C16") (pin "1") (pinfunction "1_1") (pintype "passive"))
      (node (ref "C17") (pin "1") (pinfunction "1_1") (pintype "passive"))
      (node (ref "C18") (pin "1") (pinfunction "1_1") (pintype "passive"))
      (node (ref "C19") (pin "1") (pinfunction "1_1") (pintype "passive"))
      (node (ref "C2") (pin "1") (pinfunction "1_1") (pintype "passive"))
      (node (ref "C20") (pin "1") (pinfunction "1_1") (pintype "passive"))
      (node (ref "C21") (pin "1") (pinfunction "1_1") (pintype "passive"))
      (node (ref "C22") (pin "1") (pinfunction "1_1") (pintype "passive"))
      (node (ref "C23") (pin "1") (pinfunction "1_1") (pintype "passive"))
      (node (ref "C24") (pin "1") (pinfunction "1_1") (pintype "passive"))
      (node (ref "C25") (pin "1") (pinfunction "1_1") (pintype "passive"))
      (node (ref "C26") (pin "1") (pinfunction "1_1") (pintype "passive"))
      (node (ref "C27") (pin "1") (pinfunction "1_1") (pintype "passive"))
      (node (ref "C28") (pin "1") (pinfunction "1_1") (pintype "passive"))
      (node (ref "C29") (pin "1") (pinfunction "1_1") (pintype "passive"))
      (node (ref "C3") (pin "1") (pinfunction "1_1") (pintype "passive"))
      (node (ref "C30") (pin "1") (pinfunction "1_1") (pintype "passive"))
      (node (ref "C31") (pin "1") (pinfunction "1_1") (pintype "passive"))
      (node (ref "C32") (pin "1") (pinfunction "1_1") (pintype "passive"))
      (node (ref "C33") (pin "1") (pinfunction "1_1") (pintype "passive"))
      (node (ref "C34") (pin "1") (pinfunction "1_1") (pintype "passive"))
      (node (ref "C35") (pin "1") (pinfunction "1_1") (pintype "passive"))
      (node (ref "C36") (pin "1") (pinfunction "1_1") (pintype "passive"))
      (node (ref "C37") (pin "1") (pinfunction "1_1") (pintype "passive"))
      (node (ref "C38") (pin "1") (pinfunction "1_1") (pintype "passive"))
      (node (ref "C39") (pin "1") (pinfunction "1_1") (pintype "passive"))
      (node (ref "C4") (pin "2") (pinfunction "2_2") (pintype "passive"))
      (node (ref "C40") (pin "1") (pinfunction "1_1") (pintype "passive"))
      (node (ref "C41") (pin "1") (pinfunction "1_1") (pintype "passive"))
      (node (ref "C42") (pin "1") (pinfunction "1_1") (pintype "passive"))
      (node (ref "C43") (pin "2") (pinfunction "2_2") (pintype "passive"))
      (node (ref "C46") (pin "2") (pinfunction "2_2") (pintype "passive"))
      (node (ref "C47") (pin "1") (pinfunction "1_1") (pintype "passive"))
      (node (ref "C48") (pin "1") (pinfunction "1_1") (pintype "passive"))
      (node (ref "C49") (pin "2") (pinfunction "2_2") (pintype "passive"))
      (node (ref "C5") (pin "2") (pinfunction "GND_2") (pintype "passive"))
      (node (ref "C50") (pin "2") (pinfunction "GND_2") (pintype "passive"))
      (node (ref "C51") (pin "1") (pinfunction "1_1") (pintype "passive"))
      (node (ref "C52") (pin "1") (pinfunction "1_1") (pintype "passive"))
      (node (ref "C53") (pin "1") (pinfunction "1_1") (pintype "passive"))
      (node (ref "C54") (pin "1") (pinfunction "1_1") (pintype "passive"))
      (node (ref "C55") (pin "2") (pinfunction "2_2") (pintype "passive"))
      (node (ref "C56") (pin "2") (pinfunction "2_2") (pintype "passive"))
      (node (ref "C57") (pin "2") (pinfunction "2_2") (pintype "passive"))
      (node (ref "C58") (pin "2") (pinfunction "2_2") (pintype "passive"))
      (node (ref "C59") (pin "2") (pinfunction "2_2") (pintype "passive"))
      (node (ref "C7") (pin "1") (pinfunction "1_1") (pintype "passive"))
      (node (ref "C8") (pin "1") (pinfunction "1_1") (pintype "passive"))
      (node (ref "C9") (pin "2") (pinfunction "2_2") (pintype "passive"))
      (node (ref "D12") (pin "1") (pintype "passive"))
      (node (ref "D13") (pin "1") (pintype "passive"))
      (node (ref "D2") (pin "1") (pintype "passive"))
      (node (ref "D3") (pin "3") (pintype "passive"))
      (node (ref "D5") (pin "1") (pintype "passive"))
      (node (ref "P2") (pin "3") (pinfunction "3_3") (pintype "passive"))
      (node (ref "P2") (pin "5") (pinfunction "5_5") (pintype "passive"))
      (node (ref "P2") (pin "9") (pinfunction "9_9") (pintype "passive"))
      (node (ref "Q1") (pin "3") (pinfunction "E_3") (pintype "passive"))
      (node (ref "Q10") (pin "2") (pinfunction "E_2") (pintype "passive"))
      (node (ref "Q3") (pin "2") (pinfunction "E_2") (pintype "passive"))
      (node (ref "R1") (pin "1") (pinfunction "BST_1") (pintype "passive"))
      (node (ref "R13") (pin "2") (pinfunction "BST_2") (pintype "passive"))
      (node (ref "R27") (pin "1") (pinfunction "BST_1") (pintype "passive"))
      (node (ref "R31") (pin "2") (pinfunction "BST_2") (pintype "passive"))
      (node (ref "R32") (pin "2") (pinfunction "BST_2") (pintype "passive"))
      (node (ref "R37") (pin "1") (pinfunction "BST_1") (pintype "passive"))
      (node (ref "R47") (pin "1") (pinfunction "BST_1") (pintype "passive"))
      (node (ref "R48") (pin "1") (pinfunction "BST_1") (pintype "passive"))
      (node (ref "R5") (pin "1") (pinfunction "BST_1") (pintype "passive"))
      (node (ref "R54") (pin "1") (pinfunction "BST_1") (pintype "passive"))
      (node (ref "R64") (pin "1") (pinfunction "BST_1") (pintype "passive"))
      (node (ref "U1") (pin "A4") (pinfunction "A4_A4") (pintype "passive"))
      (node (ref "U1") (pin "E4") (pinfunction "E4_E4") (pintype "passive"))
      (node (ref "U1") (pin "G4") (pinfunction "G4_G4") (pintype "passive"))
      (node (ref "U1") (pin "H2") (pinfunction "H2_H2") (pintype "passive"))
      (node (ref "U2") (pin "2") (pinfunction "GND_2") (pintype "passive"))
      (node (ref "U3") (pin "1") (pinfunction "S2_1") (pintype "passive"))
      (node (ref "U3") (pin "3") (pinfunction "S1_3") (pintype "passive"))
      (node (ref "U4") (pin "22") (pinfunction "AGND_22") (pintype "power_in"))
      (node (ref "U4") (pin "25") (pinfunction "EP_25") (pintype "power_in"))
      (node (ref "U4") (pin "6") (pinfunction "PGND_6") (pintype "power_in"))
      (node (ref "U4") (pin "9") (pinfunction "PGND_9") (pintype "power_in"))
      (node (ref "U5") (pin "10") (pinfunction "VSS/VSSA_10") (pintype "passive"))
      (node (ref "U5") (pin "40") (pinfunction "VSS_40") (pintype "passive"))
      (node (ref "U5") (pin "9") (pinfunction "VREFL_9") (pintype "passive"))
      (node (ref "U7") (pin "1") (pinfunction "GND_1") (pintype "power_in"))
      (node (ref "U7") (pin "11") (pinfunction "GND_11") (pintype "power_in"))
      (node (ref "U7") (pin "12") (pinfunction "GND_12") (pintype "power_in"))
      (node (ref "U7") (pin "2") (pinfunction "GND_2") (pintype "power_in"))
      (node (ref "U7") (pin "20") (pinfunction "GND_20") (pintype "power_in"))
    )
    (net (code "65") (name "GND_SHELL") (class "Default")
      (node (ref "C49") (pin "1") (pinfunction "1_1") (pintype "passive"))
      (node (ref "C55") (pin "1") (pinfunction "1_1") (pintype "passive"))
      (node (ref "C56") (pin "1") (pinfunction "1_1") (pintype "passive"))
      (node (ref "R13") (pin "1") (pinfunction "BST_1") (pintype "passive"))
      (node (ref "R31") (pin "1") (pinfunction "BST_1") (pintype "passive"))
      (node (ref "R32") (pin "1") (pinfunction "BST_1") (pintype "passive"))
    )
    (net (code "66") (name "Net-(D1-Pad2)") (class "Default")
      (node (ref "D1") (pin "2") (pintype "passive"))
      (node (ref "D2") (pin "2") (pintype "passive"))
      (node (ref "R51") (pin "2") (pinfunction "BST_2") (pintype "passive"))
      (node (ref "U6") (pin "1") (pinfunction "S_1") (pintype "passive"))
      (node (ref "U6") (pin "2") (pinfunction "S_2") (pintype "passive"))
      (node (ref "U6") (pin "3") (pinfunction "S_3") (pintype "passive"))
    )
    (net (code "67") (name "Net-(D4-Pad2)") (class "Default")
      (node (ref "D4") (pin "2") (pintype "passive"))
      (node (ref "D9") (pin "2") (pintype "passive"))
      (node (ref "R53") (pin "1") (pinfunction "BST_1") (pintype "passive"))
    )
    (net (code "68") (name "Net-(D6-A)") (class "Default")
      (node (ref "D6") (pin "1") (pinfunction "A_1") (pintype "passive"))
      (node (ref "R28") (pin "1") (pinfunction "BST_1") (pintype "passive"))
    )
    (net (code "69") (name "Net-(D7-A)") (class "Default")
      (node (ref "D7") (pin "1") (pinfunction "A_1") (pintype "passive"))
      (node (ref "R29") (pin "1") (pinfunction "BST_1") (pintype "passive"))
    )
    (net (code "70") (name "Net-(D8-A)") (class "Default")
      (node (ref "D8") (pin "1") (pinfunction "A_1") (pintype "passive"))
      (node (ref "R30") (pin "1") (pinfunction "BST_1") (pintype "passive"))
    )
    (net (code "71") (name "Net-(D10-Pad1)") (class "Default")
      (node (ref "D10") (pin "1") (pintype "passive"))
      (node (ref "R35") (pin "1") (pinfunction "BST_1") (pintype "passive"))
      (node (ref "R45") (pin "1") (pinfunction "BST_1") (pintype "passive"))
    )
    (net (code "72") (name "Net-(D11-Pad1)") (class "Default")
      (node (ref "D11") (pin "1") (pintype "passive"))
      (node (ref "R36") (pin "1") (pinfunction "BST_1") (pintype "passive"))
      (node (ref "R46") (pin "1") (pinfunction "BST_1") (pintype "passive"))
    )
    (net (code "73") (name "Net-(Q1-G)") (class "Default")
      (node (ref "C2") (pin "2") (pinfunction "2_2") (pintype "passive"))
      (node (ref "Q1") (pin "1") (pinfunction "G_1") (pintype "passive"))
      (node (ref "R27") (pin "2") (pinfunction "BST_2") (pintype "passive"))
      (node (ref "R9") (pin "2") (pinfunction "BST_2") (pintype "passive"))
    )
    (net (code "74") (name "Net-(Q3-B)") (class "Default")
      (node (ref "Q3") (pin "1") (pinfunction "B_1") (pintype "passive"))
      (node (ref "R53") (pin "2") (pinfunction "BST_2") (pintype "passive"))
      (node (ref "R54") (pin "2") (pinfunction "BST_2") (pintype "passive"))
    )
    (net (code "75") (name "Net-(Q3-C)") (class "Default")
      (node (ref "Q3") (pin "3") (pinfunction "C_3") (pintype "passive"))
      (node (ref "R52") (pin "1") (pinfunction "BST_1") (pintype "passive"))
    )
    (net (code "76") (name "Net-(Q10-B)") (class "Default")
      (node (ref "Q10") (pin "1") (pinfunction "B_1") (pintype "passive"))
      (node (ref "Q8") (pin "2") (pinfunction "E_2") (pintype "passive"))
      (node (ref "R64") (pin "2") (pinfunction "BST_2") (pintype "passive"))
    )
    (net (code "77") (name "Net-(Q10-C)") (class "Default")
      (node (ref "Q10") (pin "3") (pinfunction "C_3") (pintype "passive"))
      (node (ref "Q8") (pin "1") (pinfunction "B_1") (pintype "passive"))
      (node (ref "R62") (pin "1") (pinfunction "BST_1") (pintype "passive"))
    )
    (net (code "78") (name "Net-(U2-SPLIT)") (class "Default")
      (node (ref "C4") (pin "1") (pinfunction "1_1") (pintype "passive"))
      (node (ref "R2") (pin "1") (pinfunction "BST_1") (pintype "passive"))
      (node (ref "R3") (pin "2") (pinfunction "BST_2") (pintype "passive"))
      (node (ref "U2") (pin "5") (pinfunction "SPLIT_5") (pintype "passive"))
    )
    (net (code "79") (name "Net-(U2-STB)") (class "Default")
      (node (ref "R1") (pin "2") (pinfunction "BST_2") (pintype "passive"))
      (node (ref "U2") (pin "8") (pinfunction "STB_8") (pintype "passive"))
    )
    (net (code "80") (name "Net-(U3-G1)") (class "Default")
      (node (ref "R37") (pin "2") (pinfunction "BST_2") (pintype "passive"))
      (node (ref "R8") (pin "2") (pinfunction "BST_2") (pintype "passive"))
      (node (ref "U3") (pin "2") (pinfunction "G2_2") (pintype "passive"))
      (node (ref "U3") (pin "4") (pinfunction "G1_4") (pintype "passive"))
    )
    (net (code "81") (name "Net-(U4-VR_IN1)") (class "Default")
      (node (ref "C10") (pin "1") (pinfunction "1_1") (pintype "passive"))
      (node (ref "R10") (pin "2") (pinfunction "BST_2") (pintype "passive"))
      (node (ref "U4") (pin "10") (pinfunction "VR_IN1_10") (pintype "input"))
    )
    (net (code "82") (name "Net-(U4-VR_IN2)") (class "Default")
      (node (ref "C10") (pin "2") (pinfunction "2_2") (pintype "passive"))
      (node (ref "R14") (pin "2") (pinfunction "BST_2") (pintype "passive"))
      (node (ref "U4") (pin "11") (pinfunction "VR_IN2_11") (pintype "input"))
    )
    (net (code "83") (name "Net-(U4-VR_OUT)") (class "Default")
      (node (ref "R39") (pin "1") (pinfunction "BST_1") (pintype "passive"))
      (node (ref "U4") (pin "13") (pinfunction "VR_OUT_13") (pintype "output"))
    )
    (net (code "84") (name "Net-(U4-WD_DIS)") (class "Default")
      (node (ref "R12") (pin "1") (pinfunction "BST_1") (pintype "passive"))
      (node (ref "U4") (pin "12") (pinfunction "WD_DIS_12") (pintype "input"))
    )
    (net (code "85") (name "Net-(U5-PTB6{slash}XTAL{slash}KBI0_P14{slash}I2C0_SDA)") (class "Default")
      (node (ref "C24") (pin "2") (pinfunction "2_2") (pintype "passive"))
      (node (ref "R34") (pin "1") (pinfunction "BST_1") (pintype "passive"))
      (node (ref "U5") (pin "12") (pinfunction "PTB6/XTAL/KBI0_P14/I2C0_SDA_12") (pintype "passive"))
      (node (ref "X1") (pin "1") (pinfunction "1_1") (pintype "passive"))
    )
    (net (code "86") (name "Net-(U5-PTB7{slash}EXTAL{slash}KBI0_P15{slash}I2C0_SCL)") (class "Default")
      (node (ref "C25") (pin "2") (pinfunction "2_2") (pintype "passive"))
      (node (ref "R34") (pin "2") (pinfunction "BST_2") (pintype "passive"))
      (node (ref "U5") (pin "11") (pinfunction "PTB7/EXTAL/KBI0_P15/I2C0_SCL_11") (pintype "passive"))
      (node (ref "X1") (pin "2") (pinfunction "2_2") (pintype "passive"))
    )
    (net (code "87") (name "Net-(U6-G)") (class "Default")
      (node (ref "R51") (pin "1") (pinfunction "BST_1") (pintype "passive"))
      (node (ref "R52") (pin "2") (pinfunction "BST_2") (pintype "passive"))
      (node (ref "U6") (pin "4") (pinfunction "G_4") (pintype "passive"))
    )
    (net (code "88") (name "VBAT") (class "Default")
      (node (ref "D1") (pin "1") (pintype "passive"))
      (node (ref "U1") (pin "H4") (pinfunction "H4_H4") (pintype "passive"))
    )
    (net (code "89") (name "VDD5") (class "Default")
      (node (ref "C1") (pin "1") (pinfunction "1_1") (pintype "passive"))
      (node (ref "C38") (pin "2") (pinfunction "2_2") (pintype "passive"))
      (node (ref "C39") (pin "2") (pinfunction "2_2") (pintype "passive"))
      (node (ref "C40") (pin "2") (pinfunction "2_2") (pintype "passive"))
      (node (ref "C42") (pin "2") (pinfunction "2_2") (pintype "passive"))
      (node (ref "C47") (pin "2") (pinfunction "2_2") (pintype "passive"))
      (node (ref "C48") (pin "2") (pinfunction "2_2") (pintype "passive"))
      (node (ref "C57") (pin "1") (pinfunction "1_1") (pintype "passive"))
      (node (ref "L1") (pin "1") (pinfunction "1_1") (pintype "passive"))
      (node (ref "P2") (pin "1") (pinfunction "1_1") (pintype "passive"))
      (node (ref "R15") (pin "2") (pinfunction "BST_2") (pintype "passive"))
      (node (ref "R16") (pin "2") (pinfunction "BST_2") (pintype "passive"))
      (node (ref "R17") (pin "2") (pinfunction "BST_2") (pintype "passive"))
      (node (ref "R18") (pin "2") (pinfunction "BST_2") (pintype "passive"))
      (node (ref "R19") (pin "2") (pinfunction "BST_2") (pintype "passive"))
      (node (ref "R20") (pin "2") (pinfunction "BST_2") (pintype "passive"))
      (node (ref "R28") (pin "2") (pinfunction "BST_2") (pintype "passive"))
      (node (ref "R29") (pin "2") (pinfunction "BST_2") (pintype "passive"))
      (node (ref "R30") (pin "2") (pinfunction "BST_2") (pintype "passive"))
      (node (ref "R33") (pin "2") (pinfunction "BST_2") (pintype "passive"))
      (node (ref "R35") (pin "2") (pinfunction "BST_2") (pintype "passive"))
      (node (ref "R36") (pin "2") (pinfunction "BST_2") (pintype "passive"))
      (node (ref "R40") (pin "2") (pinfunction "BST_2") (pintype "passive"))
      (node (ref "R6") (pin "2") (pinfunction "BST_2") (pintype "passive"))
      (node (ref "R7") (pin "2") (pinfunction "BST_2") (pintype "passive"))
      (node (ref "U2") (pin "3") (pinfunction "VCC_3") (pintype "passive"))
      (node (ref "U5") (pin "41") (pinfunction "VDD2_41") (pintype "passive"))
      (node (ref "U5") (pin "7") (pinfunction "VDD1_7") (pintype "passive"))
      (node (ref "U5") (pin "8") (pinfunction "VDDA/VREFH_8") (pintype "passive"))
    )
    (net (code "90") (name "VDD5_EXT") (class "Default")
      (node (ref "C43") (pin "1") (pinfunction "1_1") (pintype "passive"))
      (node (ref "C9") (pin "1") (pinfunction "1_1") (pintype "passive"))
      (node (ref "L1") (pin "2") (pinfunction "2_2") (pintype "passive"))
      (node (ref "R11") (pin "2") (pinfunction "BST_2") (pintype "passive"))
      (node (ref "R12") (pin "2") (pinfunction "BST_2") (pintype "passive"))
      (node (ref "U1") (pin "E3") (pinfunction "E3_E3") (pintype "passive"))
      (node (ref "U4") (pin "21") (pinfunction "V5DD_21") (pintype "power_in"))
    )
    (net (code "91") (name "VDD12") (class "Default")
      (node (ref "C46") (pin "1") (pinfunction "1_1") (pintype "passive"))
      (node (ref "C5") (pin "1") (pinfunction "VCC_1") (pintype "passive"))
      (node (ref "C50") (pin "1") (pinfunction "VCC_1") (pintype "passive"))
      (node (ref "C8") (pin "2") (pinfunction "2_2") (pintype "passive"))
      (node (ref "R4") (pin "1") (pinfunction "BST_1") (pintype "passive"))
      (node (ref "R42") (pin "2") (pinfunction "BST_2") (pintype "passive"))
      (node (ref "U4") (pin "2") (pinfunction "VS_2") (pintype "power_in"))
      (node (ref "U6") (pin "5") (pinfunction "D_5") (pintype "passive"))
      (node (ref "U6") (pin "6") (pinfunction "6_6") (pintype "passive"))
      (node (ref "U6") (pin "7") (pinfunction "D_7") (pintype "passive"))
      (node (ref "U6") (pin "8") (pinfunction "D_8") (pintype "passive"))
      (node (ref "U7") (pin "15") (pinfunction "VS_15") (pintype "power_in"))
      (node (ref "U7") (pin "22") (pinfunction "VS_22") (pintype "power_in"))
      (node (ref "U7") (pin "4") (pinfunction "VS_4") (pintype "power_in"))
      (node (ref "U7") (pin "9") (pinfunction "VS_9") (pintype "power_in"))
    )
    (net (code "92") (name "unconnected-(P2-Pad6)") (class "Default")
      (node (ref "P2") (pin "6") (pinfunction "6_6") (pintype "passive+no_connect"))
    )
    (net (code "93") (name "unconnected-(P2-Pad7)") (class "Default")
      (node (ref "P2") (pin "7") (pinfunction "7_7") (pintype "passive+no_connect"))
    )
    (net (code "94") (name "unconnected-(P2-Pad8)") (class "Default")
      (node (ref "P2") (pin "8") (pinfunction "8_8") (pintype "passive+no_connect"))
    )
    (net (code "95") (name "unconnected-(U4-KIO-Pad1)") (class "Default")
      (node (ref "U4") (pin "1") (pinfunction "KIO_1") (pintype "bidirectional+no_connect"))
    )
    (net (code "96") (name "unconnected-(U4-RX-Pad23)") (class "Default")
      (node (ref "U4") (pin "23") (pinfunction "RX_23") (pintype "output+no_connect"))
    )
    (net (code "97") (name "unconnected-(U4-TX-Pad24)") (class "Default")
      (node (ref "U4") (pin "24") (pinfunction "TX_24") (pintype "input+no_connect"))
    )
    (net (code "98") (name "unconnected-(U5-PTA2{slash}KBI0_P2{slash}UART0_RX{slash}I2C0_SDA-Pad48)") (class "Default")
      (node (ref "U5") (pin "48") (pinfunction "PTA2/KBI0_P2/UART0_RX/I2C0_SDA_48") (pintype "passive"))
    )
    (net (code "99") (name "unconnected-(U5-PTA3{slash}KBI0_P3{slash}UART0_TX{slash}I2C0_SCL-Pad47)") (class "Default")
      (node (ref "U5") (pin "47") (pinfunction "PTA3/KBI0_P3/UART0_TX/I2C0_SCL_47") (pintype "passive"))
    )
    (net (code "100") (name "unconnected-(U5-PTC1{slash}ADC0_SE9{slash}KBI0_P17{slash}FTM2_CH1-Pad25)") (class "Default")
      (node (ref "U5") (pin "25") (pinfunction "PTC1/ADC0_SE9/KBI0_P17/FTM2_CH1_25") (pintype "passive"))
    )
    (net (code "101") (name "unconnected-(U5-PTC5{slash}KBI0_P21{slash}FTM1_CH1{slash}RTC_CLKOUT-Pad61)") (class "Default")
      (node (ref "U5") (pin "61") (pinfunction "PTC5/KBI0_P21/FTM1_CH1/RTC_CLKOUT_61") (pintype "passive"))
    )
    (net (code "102") (name "unconnected-(U5-PTD0{slash}KBI0_P24{slash}FTM2_CH2{slash}SPI1_SCK-Pad2)") (class "Default")
      (node (ref "U5") (pin "2") (pinfunction "PTD0/KBI0_P24/FTM2_CH2/SPI1_SCK_2") (pintype "passive+no_connect"))
    )
    (net (code "103") (name "unconnected-(U5-PTD3{slash}KBI0_P27{slash}SPI1_PCS-Pad45)") (class "Default")
      (node (ref "U5") (pin "45") (pinfunction "PTD3/KBI0_P27/SPI1_PCS_45") (pintype "passive"))
    )
    (net (code "104") (name "unconnected-(U5-PTD4{slash}KBI0_P28-Pad44)") (class "Default")
      (node (ref "U5") (pin "44") (pinfunction "PTD4/KBI0_P28_44") (pintype "passive"))
    )
    (net (code "105") (name "unconnected-(U5-PTE4{slash}KBI1_P4-Pad39)") (class "Default")
      (node (ref "U5") (pin "39") (pinfunction "PTE4/KBI1_P4_39") (pintype "passive"))
    )
    (net (code "106") (name "unconnected-(U5-PTF2{slash}KBI1_P10{slash}UART1_RX-Pad36)") (class "Default")
      (node (ref "U5") (pin "36") (pinfunction "PTF2/KBI1_P10/UART1_RX_36") (pintype "passive"))
    )
    (net (code "107") (name "unconnected-(U5-PTF3{slash}KBI1_P11{slash}UART1_TX-Pad35)") (class "Default")
      (node (ref "U5") (pin "35") (pinfunction "PTF3/KBI1_P11/UART1_TX_35") (pintype "passive"))
    )
    (net (code "108") (name "unconnected-(U5-PTG0{slash}KBI1_P16-Pad58)") (class "Default")
      (node (ref "U5") (pin "58") (pinfunction "PTG0/KBI1_P16_58") (pintype "passive"))
    )
    (net (code "109") (name "unconnected-(U5-PTG1{slash}KBI1_P17-Pad57)") (class "Default")
      (node (ref "U5") (pin "57") (pinfunction "PTG1/KBI1_P17_57") (pintype "passive"))
    )
    (net (code "110") (name "unconnected-(U5-PTG2{slash}KBI1_P18-Pad56)") (class "Default")
      (node (ref "U5") (pin "56") (pinfunction "PTG2/KBI1_P18_56") (pintype "passive"))
    )
    (net (code "111") (name "unconnected-(U5-PTG3{slash}KBI1_P19-Pad55)") (class "Default")
      (node (ref "U5") (pin "55") (pinfunction "PTG3/KBI1_P19_55") (pintype "passive"))
    )
    (net (code "112") (name "unconnected-(U5-PTH0{slash}KBI1_P24{slash}FTM2_CH0-Pad15)") (class "Default")
      (node (ref "U5") (pin "15") (pinfunction "PTH0/KBI1_P24/FTM2_CH0_15") (pintype "passive"))
    )
    (net (code "113") (name "unconnected-(U5-PTH1{slash}KBI1_P25{slash}FTM2_CH1-Pad14)") (class "Default")
      (node (ref "U5") (pin "14") (pinfunction "PTH1/KBI1_P25/FTM2_CH1_14") (pintype "passive"))
    )
    (net (code "114") (name "unconnected-(U5-PTH6{slash}KBI1_P30-Pad4)") (class "Default")
      (node (ref "U5") (pin "4") (pinfunction "PTH6/KBI1_P30_4") (pintype "passive"))
    )
    (net (code "115") (name "unconnected-(U5-PTH7{slash}KBI1_P31{slash}PWT_IN1-Pad3)") (class "Default")
      (node (ref "U5") (pin "3") (pinfunction "PTH7/KBI1_P31/PWT_IN1_3") (pintype "passive"))
    )
    (net (code "116") (name "unconnected-(U5-PTI4{slash}IRQ-Pad13)") (class "Default")
      (node (ref "U5") (pin "13") (pinfunction "PTI4/IRQ_13") (pintype "passive"))
    )
    (net (code "117") (name "unconnected-(U7-NC1-Pad13)") (class "Default")
      (node (ref "U7") (pin "13") (pinfunction "NC1_13") (pintype "passive+no_connect"))
    )
    (net (code "118") (name "unconnected-(U7-NC2-Pad16)") (class "Default")
      (node (ref "U7") (pin "16") (pinfunction "NC2_16") (pintype "passive+no_connect"))
    )
    (net (code "119") (name "unconnected-(U7-NC3-Pad21)") (class "Default")
      (node (ref "U7") (pin "21") (pinfunction "NC3_21") (pintype "passive+no_connect"))
    )
    (net (code "120") (name "unconnected-(U7-NC4-Pad24)") (class "Default")
      (node (ref "U7") (pin "24") (pinfunction "NC4_24") (pintype "passive+no_connect"))
    )
  )
)
